# V1_3.net
KiCad netlist of a schematic drawn in Altium Designer
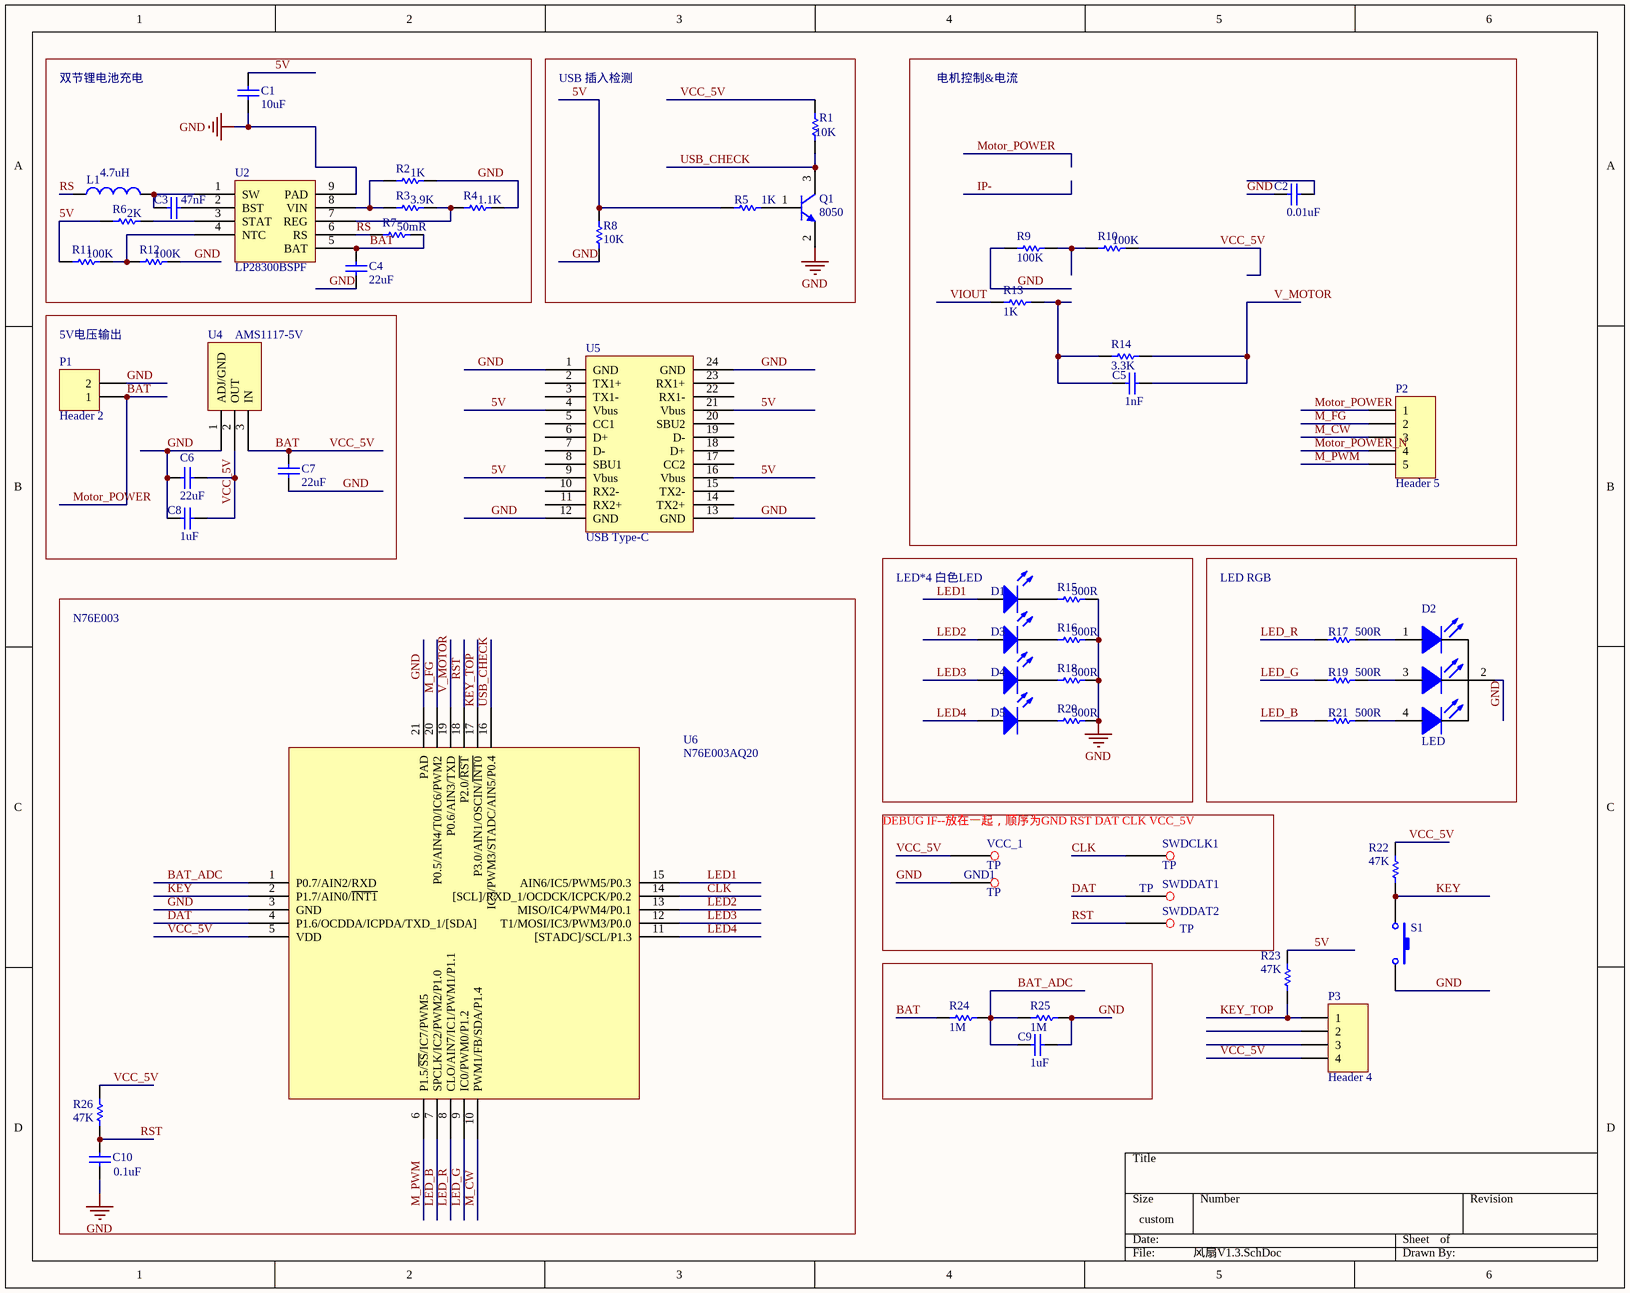
[diagram p0: 风扇V1.3.SchDoc]

(export (version "E")
  (design (tool "Eeschema 10.0.6"))
  (components
    (comp (ref "C1")
      (value "10uF")
      (footprint "c-0402")
      (description "Capacitor")
      (fields (field (name "Comment") "Cap") (field (name "PUBLISHER") "Altium Limited"))
      (libsource (lib "Miscellaneous Devices") (part "Cap"))
    )
    (comp (ref "C2")
      (value "0.01uF")
      (footprint "c-0402")
      (description "Capacitor")
      (fields (field (name "Comment") "Cap") (field (name "PUBLISHER") "Altium Limited"))
      (libsource (lib "Miscellaneous Devices") (part "Cap"))
    )
    (comp (ref "C3")
      (value "47nF")
      (footprint "c-0402")
      (description "Capacitor")
      (fields (field (name "Comment") "Cap") (field (name "PUBLISHER") "Altium Limited"))
      (libsource (lib "Miscellaneous Devices") (part "Cap"))
    )
    (comp (ref "C4")
      (value "22uF")
      (footprint "c-0402")
      (description "Capacitor")
      (fields (field (name "Comment") "Cap") (field (name "PUBLISHER") "Altium Limited"))
      (libsource (lib "Miscellaneous Devices") (part "Cap"))
    )
    (comp (ref "C5")
      (value "1nF")
      (footprint "c-0402")
      (description "Capacitor")
      (fields (field (name "Comment") "Cap") (field (name "PUBLISHER") "Altium Limited"))
      (libsource (lib "Miscellaneous Devices") (part "Cap"))
    )
    (comp (ref "C6")
      (value "22uF")
      (footprint "c-0402")
      (description "Capacitor")
      (fields (field (name "Comment") "Cap") (field (name "PUBLISHER") "Altium Limited"))
      (libsource (lib "Miscellaneous Devices") (part "Cap"))
    )
    (comp (ref "C7")
      (value "22uF")
      (footprint "c-0402")
      (description "Capacitor")
      (fields (field (name "Comment") "Cap") (field (name "PUBLISHER") "Altium Limited"))
      (libsource (lib "Miscellaneous Devices") (part "Cap"))
    )
    (comp (ref "C8")
      (value "1uF")
      (footprint "c-0402")
      (description "Capacitor")
      (fields (field (name "Comment") "Cap") (field (name "PUBLISHER") "Altium Limited"))
      (libsource (lib "Miscellaneous Devices") (part "Cap"))
    )
    (comp (ref "C9")
      (value "1uF")
      (footprint "c-0402")
      (description "Capacitor")
      (fields (field (name "Comment") "Cap") (field (name "PUBLISHER") "Altium Limited"))
      (libsource (lib "Miscellaneous Devices") (part "Cap"))
    )
    (comp (ref "C10")
      (value "0.1uF")
      (footprint "C-0402")
      (description "Capacitor")
      (fields (field (name "PUBLISHER") "Altium Limited"))
      (libsource (lib "Miscellaneous Devices") (part "Cap"))
    )
    (comp (ref "D1")
      (value "LED0")
      (footprint "Model Name")
      (description "Typical INFRARED GaAs LED")
      (fields (field (name "PUBLISHER") "Altium Limited"))
      (libsource (lib "Miscellaneous Devices") (part "LED0"))
    )
    (comp (ref "D2") (value "LED") (libsource (lib "SA2") (part "LED")))
    (comp (ref "D3")
      (value "LED0")
      (footprint "LED-0")
      (description "Typical INFRARED GaAs LED")
      (fields (field (name "PUBLISHER") "Altium Limited"))
      (libsource (lib "Miscellaneous Devices") (part "LED0"))
    )
    (comp (ref "D4")
      (value "LED0")
      (footprint "LED-0")
      (description "Typical INFRARED GaAs LED")
      (fields (field (name "PUBLISHER") "Altium Limited"))
      (libsource (lib "Miscellaneous Devices") (part "LED0"))
    )
    (comp (ref "D5")
      (value "LED0")
      (footprint "LED-0")
      (description "Typical INFRARED GaAs LED")
      (fields (field (name "PUBLISHER") "Altium Limited"))
      (libsource (lib "Miscellaneous Devices") (part "LED0"))
    )
    (comp (ref "GND1") (value "TP") (footprint "TP-1.2") (libsource (lib "Others_IC_SCH_LIB") (part "TP")))
    (comp (ref "L1")
      (value "4.7uH")
      (footprint "INDC1005AL")
      (description "Inductor")
      (fields (field (name "PUBLISHER") "Altium Limited"))
      (libsource (lib "Miscellaneous Devices") (part "Inductor"))
    )
    (comp (ref "P1")
      (value "Header 2")
      (footprint "HDR1X2")
      (description "Header, 2-Pin")
      (fields (field (name "PUBLISHER") "Altium Limited"))
      (libsource (lib "Miscellaneous Connectors") (part "Header 2"))
    )
    (comp (ref "P2")
      (value "Header 5")
      (footprint "HDR1X5")
      (description "Header, 5-Pin")
      (fields (field (name "PUBLISHER") "Altium Limited"))
      (libsource (lib "Miscellaneous Connectors") (part "Header 5"))
    )
    (comp (ref "P3")
      (value "Header 4")
      (footprint "HDR1X4")
      (description "Header, 4-Pin")
      (fields (field (name "PUBLISHER") "Altium Limited"))
      (libsource (lib "Miscellaneous Connectors") (part "Header 4"))
    )
    (comp (ref "Q1")
      (value "8050")
      (footprint "SOT-23")
      (description "NPN Bipolar Transistor")
      (fields (field (name "PUBLISHER") "Altium Limited"))
      (libsource (lib "Miscellaneous Devices") (part "NPN"))
    )
    (comp (ref "R1")
      (value "10K")
      (footprint "R-0402")
      (description "Resistor")
      (fields (field (name "PUBLISHER") "Altium Limited"))
      (libsource (lib "Miscellaneous Devices") (part "Res1"))
    )
    (comp (ref "R2")
      (value "1K")
      (footprint "R-0402")
      (description "Resistor")
      (fields (field (name "Comment") "Res1") (field (name "PUBLISHER") "Altium Limited"))
      (libsource (lib "Miscellaneous Devices") (part "Res1"))
    )
    (comp (ref "R3")
      (value "3.9K")
      (footprint "R-0402")
      (description "Resistor")
      (fields (field (name "Comment") "Res1") (field (name "PUBLISHER") "Altium Limited"))
      (libsource (lib "Miscellaneous Devices") (part "Res1"))
    )
    (comp (ref "R4")
      (value "1.1K")
      (footprint "R-0402")
      (description "Resistor")
      (fields (field (name "Comment") "Res1") (field (name "PUBLISHER") "Altium Limited"))
      (libsource (lib "Miscellaneous Devices") (part "Res1"))
    )
    (comp (ref "R5")
      (value "1K")
      (footprint "R-0402")
      (description "Resistor")
      (fields (field (name "PUBLISHER") "Altium Limited"))
      (libsource (lib "Miscellaneous Devices") (part "Res1"))
    )
    (comp (ref "R6")
      (value "2K")
      (footprint "R-0402")
      (description "Resistor")
      (fields (field (name "Comment") "Res1") (field (name "PUBLISHER") "Altium Limited"))
      (libsource (lib "Miscellaneous Devices") (part "Res1"))
    )
    (comp (ref "R7")
      (value "50mR")
      (footprint "R-0402")
      (description "Resistor")
      (fields (field (name "Comment") "Res1") (field (name "PUBLISHER") "Altium Limited"))
      (libsource (lib "Miscellaneous Devices") (part "Res1"))
    )
    (comp (ref "R8")
      (value "10K")
      (footprint "R-0402")
      (description "Resistor")
      (fields (field (name "Comment") "Res1") (field (name "PUBLISHER") "Altium Limited"))
      (libsource (lib "Miscellaneous Devices") (part "Res1"))
    )
    (comp (ref "R9")
      (value "100K")
      (footprint "R-0402")
      (description "Resistor")
      (fields (field (name "Comment") "Res1") (field (name "PUBLISHER") "Altium Limited"))
      (libsource (lib "Miscellaneous Devices") (part "Res1"))
    )
    (comp (ref "R10")
      (value "100K")
      (footprint "R-0402")
      (description "Resistor")
      (fields (field (name "Comment") "Res1") (field (name "PUBLISHER") "Altium Limited"))
      (libsource (lib "Miscellaneous Devices") (part "Res1"))
    )
    (comp (ref "R11")
      (value "100K")
      (footprint "R-0402")
      (description "Resistor")
      (fields (field (name "Comment") "Res1") (field (name "PUBLISHER") "Altium Limited"))
      (libsource (lib "Miscellaneous Devices") (part "Res1"))
    )
    (comp (ref "R12")
      (value "100K")
      (footprint "R-0402")
      (description "Resistor")
      (fields (field (name "Comment") "Res1") (field (name "PUBLISHER") "Altium Limited"))
      (libsource (lib "Miscellaneous Devices") (part "Res1"))
    )
    (comp (ref "R13")
      (value "1K")
      (footprint "R-0402")
      (description "Resistor")
      (fields (field (name "Comment") "Res1") (field (name "PUBLISHER") "Altium Limited"))
      (libsource (lib "Miscellaneous Devices") (part "Res1"))
    )
    (comp (ref "R14")
      (value "3.3K")
      (footprint "R-0402")
      (description "Resistor")
      (fields (field (name "Comment") "Res1") (field (name "PUBLISHER") "Altium Limited"))
      (libsource (lib "Miscellaneous Devices") (part "Res1"))
    )
    (comp (ref "R15")
      (value "500R")
      (footprint "R-0402")
      (description "Resistor")
      (fields (field (name "Comment") "Res1") (field (name "PUBLISHER") "Altium Limited"))
      (libsource (lib "Miscellaneous Devices") (part "Res1"))
    )
    (comp (ref "R16")
      (value "500R")
      (footprint "R-0402")
      (description "Resistor")
      (fields (field (name "Comment") "Res1") (field (name "PUBLISHER") "Altium Limited"))
      (libsource (lib "Miscellaneous Devices") (part "Res1"))
    )
    (comp (ref "R17")
      (value "500R")
      (footprint "R-0402")
      (description "Resistor")
      (fields (field (name "PUBLISHER") "Altium Limited"))
      (libsource (lib "Miscellaneous Devices") (part "Res1"))
    )
    (comp (ref "R18")
      (value "500R")
      (footprint "R-0402")
      (description "Resistor")
      (fields (field (name "Comment") "Res1") (field (name "PUBLISHER") "Altium Limited"))
      (libsource (lib "Miscellaneous Devices") (part "Res1"))
    )
    (comp (ref "R19")
      (value "500R")
      (footprint "R-0402")
      (description "Resistor")
      (fields (field (name "PUBLISHER") "Altium Limited"))
      (libsource (lib "Miscellaneous Devices") (part "Res1"))
    )
    (comp (ref "R20")
      (value "500R")
      (footprint "R-0402")
      (description "Resistor")
      (fields (field (name "Comment") "Res1") (field (name "PUBLISHER") "Altium Limited"))
      (libsource (lib "Miscellaneous Devices") (part "Res1"))
    )
    (comp (ref "R21")
      (value "500R")
      (footprint "R-0402")
      (description "Resistor")
      (fields (field (name "PUBLISHER") "Altium Limited"))
      (libsource (lib "Miscellaneous Devices") (part "Res1"))
    )
    (comp (ref "R22")
      (value "47K")
      (footprint "r-0201")
      (description "Resistor")
      (fields (field (name "Comment") "Res1") (field (name "PUBLISHER") "Altium Limited"))
      (libsource (lib "Miscellaneous Devices") (part "Res1"))
    )
    (comp (ref "R23")
      (value "47K")
      (footprint "r-0201")
      (description "Resistor")
      (fields (field (name "Comment") "Res1") (field (name "PUBLISHER") "Altium Limited"))
      (libsource (lib "Miscellaneous Devices") (part "Res1"))
    )
    (comp (ref "R24")
      (value "1M")
      (footprint "R-0402")
      (description "Resistor")
      (fields (field (name "Comment") "Res1") (field (name "PUBLISHER") "Altium Limited"))
      (libsource (lib "Miscellaneous Devices") (part "Res1"))
    )
    (comp (ref "R25")
      (value "1M")
      (footprint "R-0402")
      (description "Resistor")
      (fields (field (name "Comment") "Res1") (field (name "PUBLISHER") "Altium Limited"))
      (libsource (lib "Miscellaneous Devices") (part "Res1"))
    )
    (comp (ref "R26")
      (value "47K")
      (footprint "R-0402")
      (description "Resistor")
      (fields (field (name "PUBLISHER") "Altium Limited"))
      (libsource (lib "Miscellaneous Devices") (part "Res1"))
    )
    (comp (ref "S1")
      (value "SW-PB")
      (footprint "SWITCH")
      (description "Switch")
      (fields (field (name "PUBLISHER") "Altium Limited"))
      (libsource (lib "Miscellaneous Devices") (part "SW-PB"))
    )
    (comp (ref "SWDCLK1") (value "TP") (footprint "TP-1.2") (libsource (lib "Others_IC_SCH_LIB") (part "TP")))
    (comp (ref "SWDDAT1") (value "TP") (footprint "TP-1.2") (libsource (lib "Others_IC_SCH_LIB") (part "TP")))
    (comp (ref "SWDDAT2") (value "TP") (footprint "TP-1.2") (libsource (lib "Others_IC_SCH_LIB") (part "TP")))
    (comp (ref "U2")
      (value "LP28300BSPF")
      (footprint "ESOP8")
      (libsource (lib "Others_IC_SCH_LIB") (part "LP28300BSPF"))
    )
    (comp (ref "U4") (value "AMS1117-5V") (libsource (lib "Others_IC_SCH_LIB") (part "AMS1117")))
    (comp (ref "U5") (value "USB Type-C") (libsource (lib "Others_IC_SCH_LIB") (part "USB Type-C")))
    (comp (ref "U6")
      (value "N76E003AQ20")
      (footprint "QFN-20 0.4mm")
      (libsource (lib "Others_IC_SCH_LIB") (part "N76E003AQ20"))
    )
    (comp (ref "VCC_1") (value "TP") (footprint "TP-1.2") (libsource (lib "Others_IC_SCH_LIB") (part "TP")))
  )
  (nets
    (net (code "1") (name "/5V") (class "Default")
      (node (ref "C1") (pin "1") (pinfunction "1_1") (pintype "passive"))
      (node (ref "R11") (pin "2") (pinfunction "2_2") (pintype "passive"))
      (node (ref "R23") (pin "2") (pinfunction "2_2") (pintype "passive"))
      (node (ref "R5") (pin "1") (pinfunction "1_1") (pintype "passive"))
      (node (ref "R6") (pin "2") (pinfunction "2_2") (pintype "passive"))
      (node (ref "R8") (pin "1") (pinfunction "1_1") (pintype "passive"))
      (node (ref "U5") (pin "16") (pinfunction "Vbus_16") (pintype "passive"))
      (node (ref "U5") (pin "21") (pinfunction "Vbus_21") (pintype "passive"))
      (node (ref "U5") (pin "4") (pinfunction "Vbus_4") (pintype "passive"))
      (node (ref "U5") (pin "9") (pinfunction "Vbus_9") (pintype "passive"))
    )
    (net (code "2") (name "/BAT") (class "Default")
      (node (ref "C4") (pin "1") (pinfunction "1_1") (pintype "passive"))
      (node (ref "C6") (pin "2") (pinfunction "2_2") (pintype "passive"))
      (node (ref "C7") (pin "2") (pinfunction "2_2") (pintype "passive"))
      (node (ref "C8") (pin "2") (pinfunction "2_2") (pintype "passive"))
      (node (ref "P1") (pin "1") (pinfunction "1_1") (pintype "passive"))
      (node (ref "P2") (pin "1") (pinfunction "1_1") (pintype "passive"))
      (node (ref "P3") (pin "4") (pinfunction "4_4") (pintype "passive"))
      (node (ref "R1") (pin "2") (pinfunction "2_2") (pintype "passive"))
      (node (ref "R10") (pin "2") (pinfunction "2_2") (pintype "passive"))
      (node (ref "R22") (pin "2") (pinfunction "2_2") (pintype "passive"))
      (node (ref "R24") (pin "1") (pinfunction "1_1") (pintype "passive"))
      (node (ref "R26") (pin "2") (pinfunction "2_2") (pintype "passive"))
      (node (ref "R7") (pin "1") (pinfunction "1_1") (pintype "passive"))
      (node (ref "U2") (pin "5") (pinfunction "BAT_5") (pintype "passive"))
      (node (ref "U4") (pin "2") (pinfunction "OUT_2") (pintype "passive"))
      (node (ref "U4") (pin "3") (pinfunction "IN_3") (pintype "passive"))
      (node (ref "U6") (pin "5") (pinfunction "VDD_5") (pintype "passive"))
      (node (ref "VCC_1") (pin "1") (pinfunction "1_1") (pintype "passive"))
    )
    (net (code "3") (name "/BAT_ADC") (class "Default")
      (node (ref "C9") (pin "2") (pinfunction "2_2") (pintype "passive"))
      (node (ref "R24") (pin "2") (pinfunction "2_2") (pintype "passive"))
      (node (ref "R25") (pin "1") (pinfunction "1_1") (pintype "passive"))
      (node (ref "U6") (pin "1") (pinfunction "P0.7/AIN2/RXD_1") (pintype "passive"))
    )
    (net (code "4") (name "/CLK") (class "Default")
      (node (ref "SWDCLK1") (pin "1") (pinfunction "1_1") (pintype "passive"))
      (node (ref "U6") (pin "14") (pinfunction "[SCL]/RXD_1/OCDCK/ICPCK/P0.2_14") (pintype "passive"))
    )
    (net (code "5") (name "/DAT") (class "Default")
      (node (ref "SWDDAT1") (pin "1") (pinfunction "1_1") (pintype "passive"))
      (node (ref "U6") (pin "4") (pinfunction "P1.6/OCDDA/ICPDA/TXD_1/[SDA]_4") (pintype "passive"))
    )
    (net (code "7") (name "/KEY") (class "Default")
      (node (ref "R22") (pin "1") (pinfunction "1_1") (pintype "passive"))
      (node (ref "S1") (pin "1") (pinfunction "1_1") (pintype "passive"))
      (node (ref "U6") (pin "2") (pinfunction "P1.7/AIN0/~{INT1}_2") (pintype "passive"))
    )
    (net (code "8") (name "/KEY_TOP") (class "Default")
      (node (ref "P3") (pin "1") (pinfunction "1_1") (pintype "passive"))
      (node (ref "R23") (pin "1") (pinfunction "1_1") (pintype "passive"))
      (node (ref "U6") (pin "17") (pinfunction "P3.0/AIN1/OSCIN/~{INT0}_17") (pintype "passive"))
    )
    (net (code "9") (name "/LED1") (class "Default")
      (node (ref "D1") (pin "1") (pinfunction "A_1") (pintype "passive"))
      (node (ref "U6") (pin "15") (pinfunction "AIN6/IC5/PWM5/P0.3_15") (pintype "passive"))
    )
    (net (code "10") (name "/LED2") (class "Default")
      (node (ref "D3") (pin "1") (pinfunction "A_1") (pintype "passive"))
      (node (ref "U6") (pin "13") (pinfunction "MISO/IC4/PWM4/P0.1_13") (pintype "passive"))
    )
    (net (code "11") (name "/LED3") (class "Default")
      (node (ref "D4") (pin "1") (pinfunction "A_1") (pintype "passive"))
      (node (ref "U6") (pin "12") (pinfunction "T1/MOSI/IC3/PWM3/P0.0_12") (pintype "passive"))
    )
    (net (code "12") (name "/LED4") (class "Default")
      (node (ref "D5") (pin "1") (pinfunction "A_1") (pintype "passive"))
      (node (ref "U6") (pin "11") (pinfunction "[STADC]/SCL/P1.3_11") (pintype "passive"))
    )
    (net (code "13") (name "/LED_B") (class "Default")
      (node (ref "R21") (pin "1") (pinfunction "1_1") (pintype "passive"))
      (node (ref "U6") (pin "7") (pinfunction "SPCLK/IC2/PWM2/P1.0_7") (pintype "passive"))
    )
    (net (code "14") (name "/LED_G") (class "Default")
      (node (ref "R19") (pin "1") (pinfunction "1_1") (pintype "passive"))
      (node (ref "U6") (pin "9") (pinfunction "IC0/PWM0/P1.2_9") (pintype "passive"))
    )
    (net (code "15") (name "/LED_R") (class "Default")
      (node (ref "R17") (pin "1") (pinfunction "1_1") (pintype "passive"))
      (node (ref "U6") (pin "8") (pinfunction "CLO/AIN7/IC1/PWM1/P1.1_8") (pintype "passive"))
    )
    (net (code "16") (name "/M_CW") (class "Default")
      (node (ref "P2") (pin "3") (pinfunction "3_3") (pintype "passive"))
      (node (ref "U6") (pin "10") (pinfunction "PWM1/FB/SDA/P1.4_10") (pintype "passive"))
    )
    (net (code "17") (name "/M_FG") (class "Default")
      (node (ref "P2") (pin "2") (pinfunction "2_2") (pintype "passive"))
      (node (ref "U6") (pin "20") (pinfunction "P0.5/AIN4/T0/IC6/PWM2_20") (pintype "passive"))
    )
    (net (code "18") (name "/M_PWM") (class "Default")
      (node (ref "P2") (pin "5") (pinfunction "5_5") (pintype "passive"))
      (node (ref "U6") (pin "6") (pinfunction "P1.5/~{SS}/IC7/PWM5_6") (pintype "passive"))
    )
    (net (code "19") (name "/Motor_POWER_N") (class "Default")
      (node (ref "P2") (pin "4") (pinfunction "4_4") (pintype "passive"))
    )
    (net (code "20") (name "/RS") (class "Default")
      (node (ref "L1") (pin "1") (pinfunction "1_1") (pintype "passive"))
      (node (ref "R7") (pin "2") (pinfunction "2_2") (pintype "passive"))
      (node (ref "U2") (pin "6") (pinfunction "RS_6") (pintype "passive"))
    )
    (net (code "21") (name "/RST") (class "Default")
      (node (ref "C10") (pin "2") (pinfunction "2_2") (pintype "passive"))
      (node (ref "R26") (pin "1") (pinfunction "1_1") (pintype "passive"))
      (node (ref "SWDDAT2") (pin "1") (pinfunction "1_1") (pintype "passive"))
      (node (ref "U6") (pin "18") (pinfunction "P2.0/~{RST}_18") (pintype "passive"))
    )
    (net (code "22") (name "/USB_CHECK") (class "Default")
      (node (ref "Q1") (pin "3") (pinfunction "C_3") (pintype "passive"))
      (node (ref "R1") (pin "1") (pinfunction "1_1") (pintype "passive"))
      (node (ref "U6") (pin "16") (pinfunction "IC3/PWM3/STADC/AIN5/P0.4_16") (pintype "passive"))
    )
    (net (code "23") (name "/VIOUT") (class "Default")
      (node (ref "R13") (pin "1") (pinfunction "1_1") (pintype "passive"))
    )
    (net (code "24") (name "/V_MOTOR") (class "Default")
      (node (ref "C5") (pin "1") (pinfunction "1_1") (pintype "passive"))
      (node (ref "R14") (pin "2") (pinfunction "2_2") (pintype "passive"))
      (node (ref "U6") (pin "19") (pinfunction "P0.6/AIN3/TXD_19") (pintype "passive"))
    )
    (net (code "25") (name "GND") (class "Default")
      (node (ref "C1") (pin "2") (pinfunction "2_2") (pintype "passive"))
      (node (ref "C10") (pin "1") (pinfunction "1_1") (pintype "passive"))
      (node (ref "C2") (pin "2") (pinfunction "2_2") (pintype "passive"))
      (node (ref "C4") (pin "2") (pinfunction "2_2") (pintype "passive"))
      (node (ref "C6") (pin "1") (pinfunction "1_1") (pintype "passive"))
      (node (ref "C7") (pin "1") (pinfunction "1_1") (pintype "passive"))
      (node (ref "C8") (pin "1") (pinfunction "1_1") (pintype "passive"))
      (node (ref "C9") (pin "1") (pinfunction "1_1") (pintype "passive"))
      (node (ref "D2") (pin "2") (pinfunction "2_2") (pintype "passive"))
      (node (ref "GND1") (pin "1") (pinfunction "1_1") (pintype "passive"))
      (node (ref "P1") (pin "2") (pinfunction "2_2") (pintype "passive"))
      (node (ref "Q1") (pin "2") (pinfunction "E_2") (pintype "passive"))
      (node (ref "R12") (pin "1") (pinfunction "1_1") (pintype "passive"))
      (node (ref "R15") (pin "2") (pinfunction "2_2") (pintype "passive"))
      (node (ref "R16") (pin "2") (pinfunction "2_2") (pintype "passive"))
      (node (ref "R18") (pin "2") (pinfunction "2_2") (pintype "passive"))
      (node (ref "R2") (pin "1") (pinfunction "1_1") (pintype "passive"))
      (node (ref "R20") (pin "2") (pinfunction "2_2") (pintype "passive"))
      (node (ref "R25") (pin "2") (pinfunction "2_2") (pintype "passive"))
      (node (ref "R4") (pin "1") (pinfunction "1_1") (pintype "passive"))
      (node (ref "R8") (pin "2") (pinfunction "2_2") (pintype "passive"))
      (node (ref "R9") (pin "1") (pinfunction "1_1") (pintype "passive"))
      (node (ref "S1") (pin "2") (pinfunction "2_2") (pintype "passive"))
      (node (ref "U2") (pin "9") (pinfunction "PAD_9") (pintype "passive"))
      (node (ref "U4") (pin "1") (pinfunction "ADJ/GND_1") (pintype "passive"))
      (node (ref "U5") (pin "1") (pinfunction "GND_1") (pintype "passive"))
      (node (ref "U5") (pin "12") (pinfunction "GND_12") (pintype "passive"))
      (node (ref "U5") (pin "13") (pinfunction "GND_13") (pintype "passive"))
      (node (ref "U5") (pin "24") (pinfunction "GND_24") (pintype "passive"))
      (node (ref "U6") (pin "21") (pinfunction "PAD_21") (pintype "passive"))
      (node (ref "U6") (pin "3") (pinfunction "GND_3") (pintype "passive"))
    )
    (net (code "26") (name "Net-(C5-Pad2)") (class "Default")
      (node (ref "C5") (pin "2") (pinfunction "2_2") (pintype "passive"))
      (node (ref "R13") (pin "2") (pinfunction "2_2") (pintype "passive"))
      (node (ref "R14") (pin "1") (pinfunction "1_1") (pintype "passive"))
    )
    (net (code "27") (name "Net-(D1-K)") (class "Default")
      (node (ref "D1") (pin "2") (pinfunction "K_2") (pintype "passive"))
      (node (ref "R15") (pin "1") (pinfunction "1_1") (pintype "passive"))
    )
    (net (code "28") (name "Net-(D2-Pad1)") (class "Default")
      (node (ref "D2") (pin "1") (pinfunction "1_1") (pintype "passive"))
      (node (ref "R17") (pin "2") (pinfunction "2_2") (pintype "passive"))
    )
    (net (code "29") (name "Net-(D2-Pad3)") (class "Default")
      (node (ref "D2") (pin "3") (pinfunction "3_3") (pintype "passive"))
      (node (ref "R19") (pin "2") (pinfunction "2_2") (pintype "passive"))
    )
    (net (code "30") (name "Net-(D2-Pad4)") (class "Default")
      (node (ref "D2") (pin "4") (pinfunction "4_4") (pintype "passive"))
      (node (ref "R21") (pin "2") (pinfunction "2_2") (pintype "passive"))
    )
    (net (code "31") (name "Net-(D3-K)") (class "Default")
      (node (ref "D3") (pin "2") (pinfunction "K_2") (pintype "passive"))
      (node (ref "R16") (pin "1") (pinfunction "1_1") (pintype "passive"))
    )
    (net (code "32") (name "Net-(D4-K)") (class "Default")
      (node (ref "D4") (pin "2") (pinfunction "K_2") (pintype "passive"))
      (node (ref "R18") (pin "1") (pinfunction "1_1") (pintype "passive"))
    )
    (net (code "33") (name "Net-(D5-K)") (class "Default")
      (node (ref "D5") (pin "2") (pinfunction "K_2") (pintype "passive"))
      (node (ref "R20") (pin "1") (pinfunction "1_1") (pintype "passive"))
    )
    (net (code "34") (name "Net-(Q1-B)") (class "Default")
      (node (ref "Q1") (pin "1") (pinfunction "B_1") (pintype "passive"))
      (node (ref "R5") (pin "2") (pinfunction "2_2") (pintype "passive"))
    )
    (net (code "35") (name "Net-(R10-Pad1)") (class "Default")
      (node (ref "R10") (pin "1") (pinfunction "1_1") (pintype "passive"))
      (node (ref "R9") (pin "2") (pinfunction "2_2") (pintype "passive"))
    )
    (net (code "36") (name "Net-(U2-BST)") (class "Default")
      (node (ref "C3") (pin "2") (pinfunction "2_2") (pintype "passive"))
      (node (ref "U2") (pin "2") (pinfunction "BST_2") (pintype "passive"))
    )
    (net (code "37") (name "Net-(U2-NTC)") (class "Default")
      (node (ref "R11") (pin "1") (pinfunction "1_1") (pintype "passive"))
      (node (ref "R12") (pin "2") (pinfunction "2_2") (pintype "passive"))
      (node (ref "U2") (pin "4") (pinfunction "NTC_4") (pintype "passive"))
    )
    (net (code "38") (name "Net-(U2-REG)") (class "Default")
      (node (ref "R3") (pin "1") (pinfunction "1_1") (pintype "passive"))
      (node (ref "R4") (pin "2") (pinfunction "2_2") (pintype "passive"))
      (node (ref "U2") (pin "7") (pinfunction "REG_7") (pintype "passive"))
    )
    (net (code "39") (name "Net-(U2-STAT)") (class "Default")
      (node (ref "R6") (pin "1") (pinfunction "1_1") (pintype "passive"))
      (node (ref "U2") (pin "3") (pinfunction "STAT_3") (pintype "passive"))
    )
    (net (code "40") (name "Net-(U2-SW)") (class "Default")
      (node (ref "C3") (pin "1") (pinfunction "1_1") (pintype "passive"))
      (node (ref "L1") (pin "2") (pinfunction "2_2") (pintype "passive"))
      (node (ref "U2") (pin "1") (pinfunction "SW_1") (pintype "passive"))
    )
    (net (code "41") (name "Net-(U2-VIN)") (class "Default")
      (node (ref "R2") (pin "2") (pinfunction "2_2") (pintype "passive"))
      (node (ref "R3") (pin "2") (pinfunction "2_2") (pintype "passive"))
      (node (ref "U2") (pin "8") (pinfunction "VIN_8") (pintype "passive"))
    )
    (net (code "42") (name "unconnected-(C2-Pad1)") (class "Default")
      (node (ref "C2") (pin "1") (pinfunction "1_1") (pintype "passive"))
    )
    (net (code "43") (name "unconnected-(P3-Pad2)") (class "Default")
      (node (ref "P3") (pin "2") (pinfunction "2_2") (pintype "passive"))
    )
    (net (code "44") (name "unconnected-(P3-Pad3)") (class "Default")
      (node (ref "P3") (pin "3") (pinfunction "3_3") (pintype "passive"))
    )
    (net (code "45") (name "unconnected-(U5-CC1-Pad5)") (class "Default")
      (node (ref "U5") (pin "5") (pinfunction "CC1_5") (pintype "passive"))
    )
    (net (code "46") (name "unconnected-(U5-CC2-Pad17)") (class "Default")
      (node (ref "U5") (pin "17") (pinfunction "CC2_17") (pintype "passive"))
    )
    (net (code "47") (name "unconnected-(U5-D+-Pad6)") (class "Default")
      (node (ref "U5") (pin "6") (pinfunction "D+_6") (pintype "passive"))
    )
    (net (code "48") (name "unconnected-(U5-D+-Pad18)") (class "Default")
      (node (ref "U5") (pin "18") (pinfunction "D+_18") (pintype "passive"))
    )
    (net (code "49") (name "unconnected-(U5-D--Pad7)") (class "Default")
      (node (ref "U5") (pin "7") (pinfunction "D-_7") (pintype "passive"))
    )
    (net (code "50") (name "unconnected-(U5-D--Pad19)") (class "Default")
      (node (ref "U5") (pin "19") (pinfunction "D-_19") (pintype "passive"))
    )
    (net (code "51") (name "unconnected-(U5-RX1+-Pad23)") (class "Default")
      (node (ref "U5") (pin "23") (pinfunction "RX1+_23") (pintype "passive"))
    )
    (net (code "52") (name "unconnected-(U5-RX1--Pad22)") (class "Default")
      (node (ref "U5") (pin "22") (pinfunction "RX1-_22") (pintype "passive"))
    )
    (net (code "53") (name "unconnected-(U5-RX2+-Pad11)") (class "Default")
      (node (ref "U5") (pin "11") (pinfunction "RX2+_11") (pintype "passive"))
    )
    (net (code "54") (name "unconnected-(U5-RX2--Pad10)") (class "Default")
      (node (ref "U5") (pin "10") (pinfunction "RX2-_10") (pintype "passive"))
    )
    (net (code "55") (name "unconnected-(U5-SBU1-Pad8)") (class "Default")
      (node (ref "U5") (pin "8") (pinfunction "SBU1_8") (pintype "passive"))
    )
    (net (code "56") (name "unconnected-(U5-SBU2-Pad20)") (class "Default")
      (node (ref "U5") (pin "20") (pinfunction "SBU2_20") (pintype "passive"))
    )
    (net (code "57") (name "unconnected-(U5-TX1+-Pad2)") (class "Default")
      (node (ref "U5") (pin "2") (pinfunction "TX1+_2") (pintype "passive"))
    )
    (net (code "58") (name "unconnected-(U5-TX1--Pad3)") (class "Default")
      (node (ref "U5") (pin "3") (pinfunction "TX1-_3") (pintype "passive"))
    )
    (net (code "59") (name "unconnected-(U5-TX2+-Pad14)") (class "Default")
      (node (ref "U5") (pin "14") (pinfunction "TX2+_14") (pintype "passive"))
    )
    (net (code "60") (name "unconnected-(U5-TX2--Pad15)") (class "Default")
      (node (ref "U5") (pin "15") (pinfunction "TX2-_15") (pintype "passive"))
    )
  )
)
